# EEPROM.net
KiCad netlist of a schematic drawn in Altium Designer
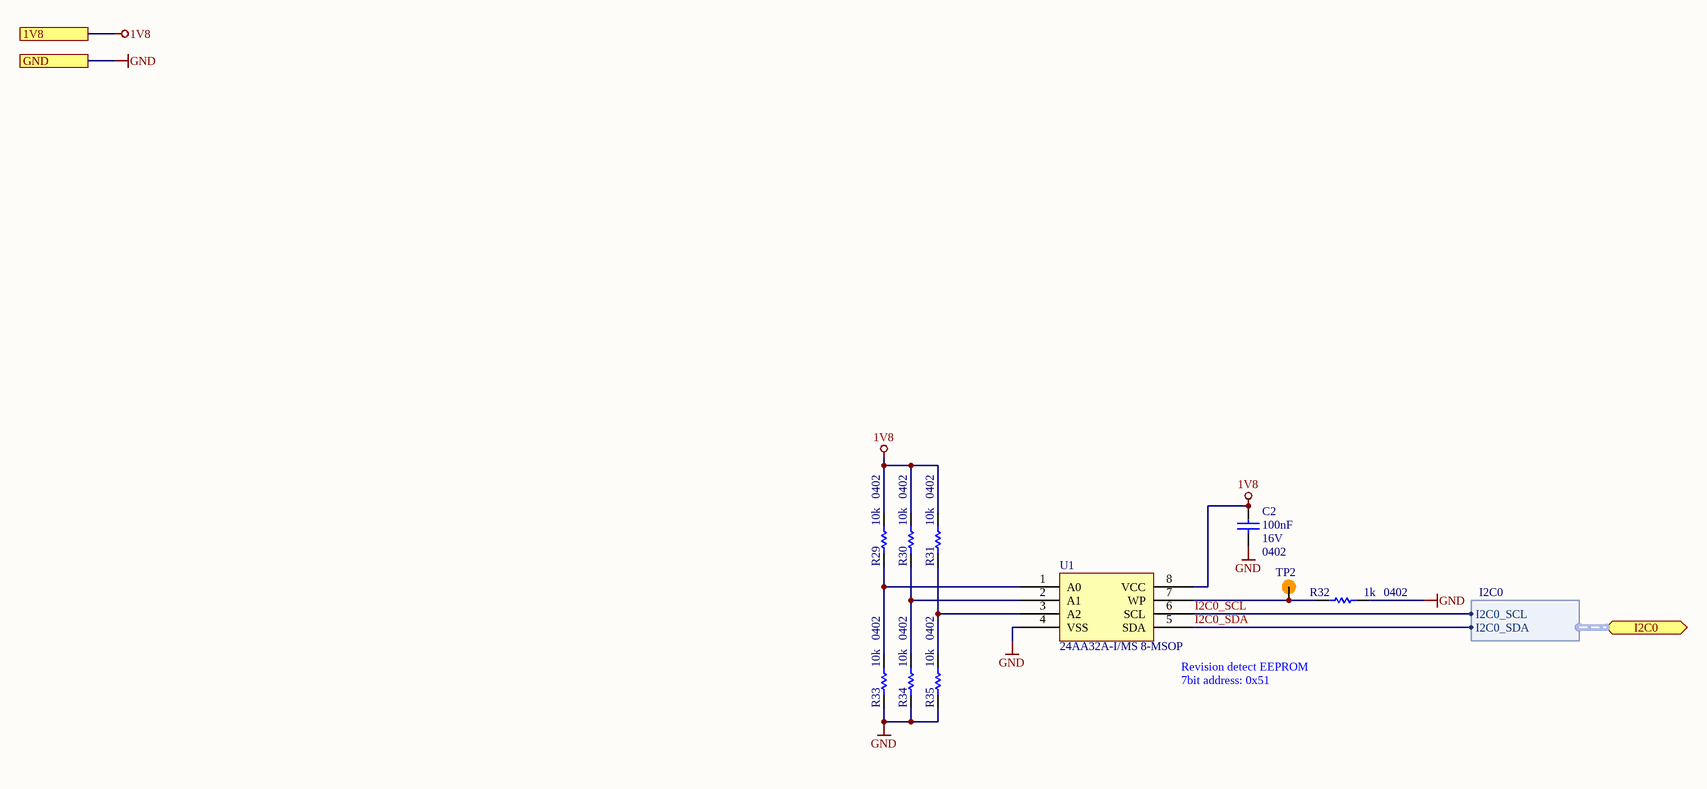
[diagram p0: EEPROM.SchDoc]

(export (version "E")
  (design (tool "Eeschema 10.0.6"))
  (components
    (comp (ref "C2")
      (value "100nF")
      (footprint "CAPC0402(1005)60_N")
      (description "CAP CER 0.1UF 16V X7R 0402 10%")
      (fields
        (field (name "VOLTAGE RATING") "16V")
        (field (name "CASE/PACKAGE") "0402")
        (field (name "TOLERANCE") "10%")
        (field (name "Comment") "CL05B104KO5NFNC")
      )
      (libsource (lib "Luxonis LLC") (part "GRM188R61C475KAAJD"))
    )
    (comp (ref "R29")
      (value "10k")
      (footprint "RESC0402(1005)_N")
      (description "RES SMD 10K OHM 1% 1/16W 0402")
      (fields
        (field (name "CASE/PACKAGE") "0402")
        (field (name "TOLERANCE") "1%")
        (field (name "Comment") "RC0402FR-1310KL")
      )
      (libsource (lib "Luxonis LLC") (part "RC0402FR-0722RL_1"))
    )
    (comp (ref "R30")
      (value "10k")
      (footprint "RESC0402(1005)_N")
      (description "RES SMD 10K OHM 1% 1/16W 0402")
      (fields
        (field (name "CASE/PACKAGE") "0402")
        (field (name "TOLERANCE") "1%")
        (field (name "Comment") "RC0402FR-1310KL")
      )
      (libsource (lib "Luxonis LLC") (part "RC0402FR-0722RL_1"))
    )
    (comp (ref "R31")
      (value "10k")
      (footprint "RESC0402(1005)_N")
      (description "RES SMD 10K OHM 1% 1/16W 0402")
      (fields
        (field (name "CASE/PACKAGE") "0402")
        (field (name "TOLERANCE") "1%")
        (field (name "Comment") "RC0402FR-1310KL")
      )
      (libsource (lib "Luxonis LLC") (part "RC0402FR-0722RL_1"))
    )
    (comp (ref "R32")
      (value "1k")
      (footprint "RESC0402(1005)_L")
      (description "RES SMD 1K OHM 1% 1/16W 0402")
      (fields
        (field (name "CASE/PACKAGE") "0402")
        (field (name "TOLERANCE") "1%")
        (field (name "Comment") "RC0402FR-071KL")
      )
      (libsource (lib "Luxonis LLC") (part "Default resistor symbol"))
    )
    (comp (ref "R33")
      (value "10k")
      (footprint "RESC0402(1005)_N")
      (description "RES SMD 10K OHM 1% 1/16W 0402")
      (fields
        (field (name "CASE/PACKAGE") "0402")
        (field (name "TOLERANCE") "1%")
        (field (name "Comment") "RC0402FR-1310KL")
      )
      (libsource (lib "Luxonis LLC") (part "RC0402FR-0722RL_1"))
    )
    (comp (ref "R34")
      (value "10k")
      (footprint "RESC0402(1005)_N")
      (description "RES SMD 10K OHM 1% 1/16W 0402")
      (fields
        (field (name "CASE/PACKAGE") "0402")
        (field (name "TOLERANCE") "1%")
        (field (name "Comment") "RC0402FR-1310KL")
      )
      (libsource (lib "Luxonis LLC") (part "RC0402FR-0722RL_1"))
    )
    (comp (ref "R35")
      (value "10k")
      (footprint "RESC0402(1005)_N")
      (description "RES SMD 10K OHM 1% 1/16W 0402")
      (fields
        (field (name "CASE/PACKAGE") "0402")
        (field (name "TOLERANCE") "1%")
        (field (name "Comment") "RC0402FR-1310KL")
      )
      (libsource (lib "Luxonis LLC") (part "RC0402FR-0722RL_1"))
    )
    (comp (ref "TP2")
      (value "TP075_150_NS")
      (footprint "LuxonisMaster:TP075_150_NS")
      (libsource (lib "LuxonisMaster") (part "TEST_POINT"))
    )
    (comp (ref "U1")
      (value "24AA32A-I/MS 8-MSOP")
      (footprint "LuxonisMaster:24AA32A-I/MS")
      (description "IC EEPROM 32K I2C 400KHZ 8MSOP Memory IC 32Kb (4K x 8) I²C 400kHz 900ns 8-MSOP")
      (libsource (lib "LuxonisMaster") (part "24AA32A-I/MS"))
    )
  )
  (nets
    (net (code "2") (name "/I2C0_SCL") (class "Default")
      (node (ref "U1") (pin "6") (pinfunction "SCL_6") (pintype "passive"))
    )
    (net (code "3") (name "/I2C0_SDA") (class "Default")
      (node (ref "U1") (pin "5") (pinfunction "SDA_5") (pintype "passive"))
    )
    (net (code "5") (name "1V8") (class "Default")
      (node (ref "C2") (pin "2") (pinfunction "2_2") (pintype "passive"))
      (node (ref "R29") (pin "2") (pinfunction "2_2") (pintype "passive"))
      (node (ref "R30") (pin "2") (pinfunction "2_2") (pintype "passive"))
      (node (ref "R31") (pin "2") (pinfunction "2_2") (pintype "passive"))
      (node (ref "U1") (pin "8") (pinfunction "VCC_8") (pintype "passive"))
    )
    (net (code "6") (name "GND") (class "Default")
      (node (ref "C2") (pin "1") (pinfunction "1_1") (pintype "passive"))
      (node (ref "R32") (pin "1") (pinfunction "1_1") (pintype "passive"))
      (node (ref "R33") (pin "1") (pinfunction "1_1") (pintype "passive"))
      (node (ref "R34") (pin "1") (pinfunction "1_1") (pintype "passive"))
      (node (ref "R35") (pin "1") (pinfunction "1_1") (pintype "passive"))
      (node (ref "U1") (pin "4") (pinfunction "VSS_4") (pintype "passive"))
    )
    (net (code "7") (name "Net-(U1-A0)") (class "Default")
      (node (ref "R29") (pin "1") (pinfunction "1_1") (pintype "passive"))
      (node (ref "R33") (pin "2") (pinfunction "2_2") (pintype "passive"))
      (node (ref "U1") (pin "1") (pinfunction "A0_1") (pintype "passive"))
    )
    (net (code "8") (name "Net-(U1-A1)") (class "Default")
      (node (ref "R30") (pin "1") (pinfunction "1_1") (pintype "passive"))
      (node (ref "R34") (pin "2") (pinfunction "2_2") (pintype "passive"))
      (node (ref "U1") (pin "2") (pinfunction "A1_2") (pintype "passive"))
    )
    (net (code "9") (name "Net-(U1-A2)") (class "Default")
      (node (ref "R31") (pin "1") (pinfunction "1_1") (pintype "passive"))
      (node (ref "R35") (pin "2") (pinfunction "2_2") (pintype "passive"))
      (node (ref "U1") (pin "3") (pinfunction "A2_3") (pintype "passive"))
    )
    (net (code "10") (name "Net-(U1-WP)") (class "Default")
      (node (ref "R32") (pin "2") (pinfunction "2_2") (pintype "passive"))
      (node (ref "TP2") (pin "1") (pintype "passive"))
      (node (ref "U1") (pin "7") (pinfunction "WP_7") (pintype "passive"))
    )
  )
)
